# untitled.net
KiCad netlist of a schematic drawn in EAGLE
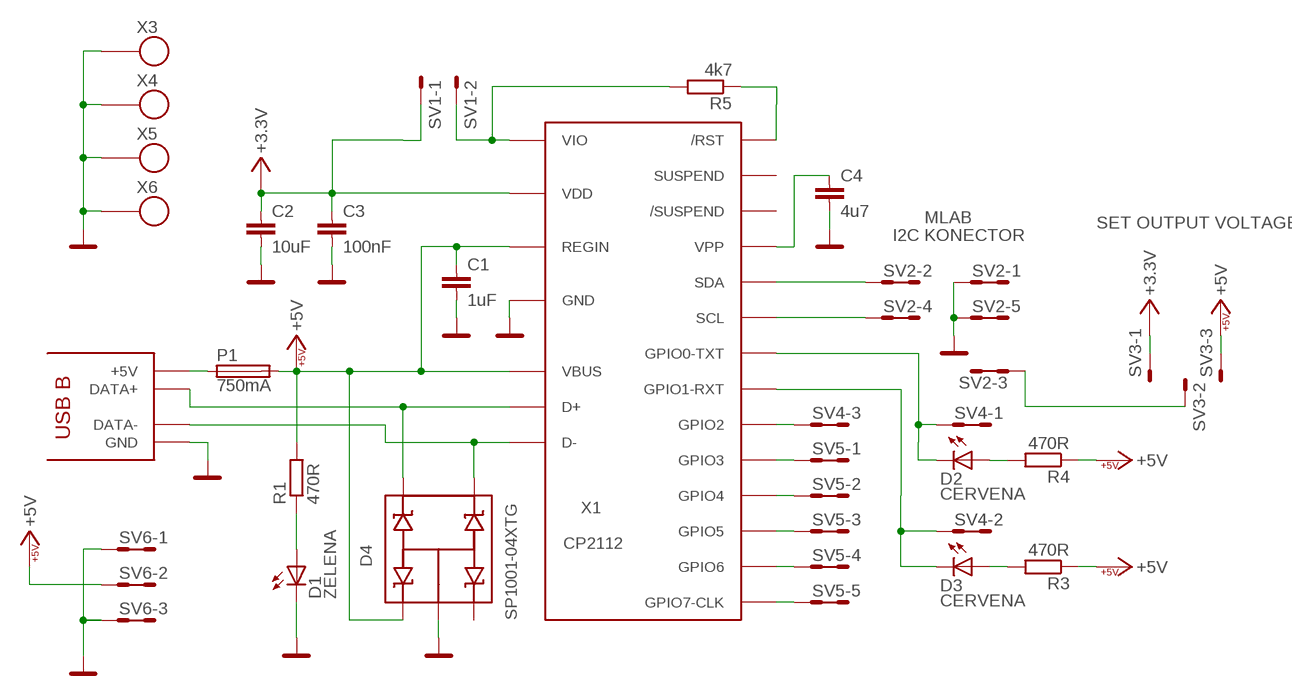
[diagram p0: schematic, sheet 1]

(export (version "E")
  (design (tool "Eeschema 10.0.6"))
  (components
    (comp (ref "C1")
      (value "1uF")
      (footprint "eagle-import:C0805")
      (libsource (lib "eagle-import") (part "C0805"))
    )
    (comp (ref "C2")
      (value "10uF")
      (footprint "eagle-import:C0805")
      (libsource (lib "eagle-import") (part "C0805"))
    )
    (comp (ref "C3")
      (value "100nF")
      (footprint "eagle-import:C0805")
      (libsource (lib "eagle-import") (part "C0805"))
    )
    (comp (ref "C4")
      (value "4u7")
      (footprint "eagle-import:C0805")
      (libsource (lib "eagle-import") (part "C0805"))
    )
    (comp (ref "D1")
      (value "ZELENA")
      (footprint "eagle-import:1206_2")
      (libsource (lib "eagle-import") (part "LED1206_2"))
    )
    (comp (ref "D2")
      (value "CERVENA")
      (footprint "eagle-import:1206_2")
      (libsource (lib "eagle-import") (part "LED1206_2"))
    )
    (comp (ref "D3")
      (value "CERVENA")
      (footprint "eagle-import:1206_2")
      (libsource (lib "eagle-import") (part "LED1206_2"))
    )
    (comp (ref "D4")
      (value "SP1001-04XTG")
      (footprint "eagle-import:SOT553")
      (libsource (lib "eagle-import") (part "CP2112"))
    )
    (comp (ref "P1")
      (value "750mA")
      (footprint "eagle-import:1812")
      (libsource (lib "eagle-import") (part "POJISTKA_1812"))
    )
    (comp (ref "R1")
      (value "470R")
      (footprint "eagle-import:0805")
      (libsource (lib "eagle-import") (part "R0805"))
    )
    (comp (ref "R3")
      (value "470R")
      (footprint "eagle-import:0805")
      (libsource (lib "eagle-import") (part "R0805"))
    )
    (comp (ref "R4")
      (value "470R")
      (footprint "eagle-import:0805")
      (libsource (lib "eagle-import") (part "R0805"))
    )
    (comp (ref "R5")
      (value "4k7")
      (footprint "eagle-import:0805")
      (libsource (lib "eagle-import") (part "R0805"))
    )
    (comp (ref "SV1")
      (value "MA02-1")
      (footprint "eagle-import:MA02-1")
      (libsource (lib "eagle-import") (part "MA02-1"))
    )
    (comp (ref "SV2")
      (value "MA05-2")
      (footprint "eagle-import:MA05-2")
      (libsource (lib "eagle-import") (part "MA05-2"))
    )
    (comp (ref "SV3")
      (value "MA03-1")
      (footprint "eagle-import:MA03-1")
      (libsource (lib "eagle-import") (part "MA03-1"))
    )
    (comp (ref "SV4")
      (value "MA03-2")
      (footprint "eagle-import:MA03-2")
      (libsource (lib "eagle-import") (part "MA03-2"))
    )
    (comp (ref "SV5")
      (value "MA05-2")
      (footprint "eagle-import:MA05-2")
      (libsource (lib "eagle-import") (part "MA05-2"))
    )
    (comp (ref "SV6")
      (value "MA03-2")
      (footprint "eagle-import:MA03-2")
      (libsource (lib "eagle-import") (part "MA03-2"))
    )
    (comp (ref "X1")
      (value "CP2112")
      (footprint "eagle-import:QFN-24")
      (libsource (lib "eagle-import") (part "moje_io_CP2112"))
    )
    (comp (ref "X2")
      (value "USB_B")
      (footprint "eagle-import:USB_B")
      (libsource (lib "eagle-import") (part "USB_B"))
    )
    (comp (ref "X3")
      (value "SROUB3M")
      (footprint "eagle-import:SROUB3M")
      (libsource (lib "eagle-import") (part "SROUB3M"))
    )
    (comp (ref "X4")
      (value "SROUB3M")
      (footprint "eagle-import:SROUB3M")
      (libsource (lib "eagle-import") (part "SROUB3M"))
    )
    (comp (ref "X5")
      (value "SROUB3M")
      (footprint "eagle-import:SROUB3M")
      (libsource (lib "eagle-import") (part "SROUB3M"))
    )
    (comp (ref "X6")
      (value "SROUB3M")
      (footprint "eagle-import:SROUB3M")
      (libsource (lib "eagle-import") (part "SROUB3M"))
    )
  )
  (nets
    (net (code "1") (name "+3.3V") (class "Default")
      (node (ref "C2") (pin "1") (pinfunction "1_1") (pintype "passive"))
      (node (ref "C3") (pin "1") (pinfunction "1_1") (pintype "passive"))
      (node (ref "SV1") (pin "1") (pinfunction "P$1_1") (pintype "passive"))
      (node (ref "SV3") (pin "1") (pinfunction "P$1_1") (pintype "passive"))
      (node (ref "X1") (pin "P$6") (pinfunction "VDD_P$6") (pintype "bidirectional"))
    )
    (net (code "2") (name "+5V") (class "Default")
      (node (ref "C1") (pin "1") (pinfunction "1_1") (pintype "passive"))
      (node (ref "D4") (pin "1") (pinfunction "P$1_1") (pintype "passive"))
      (node (ref "P1") (pin "2") (pinfunction "2_2") (pintype "passive"))
      (node (ref "R1") (pin "2") (pinfunction "2_2") (pintype "passive"))
      (node (ref "R3") (pin "1") (pinfunction "1_1") (pintype "passive"))
      (node (ref "R4") (pin "1") (pinfunction "1_1") (pintype "passive"))
      (node (ref "SV3") (pin "3") (pinfunction "P$1_3") (pintype "passive"))
      (node (ref "SV6") (pin "3") (pinfunction "K_3") (pintype "passive"))
      (node (ref "SV6") (pin "4") (pinfunction "K_4") (pintype "passive"))
      (node (ref "X1") (pin "P$7") (pinfunction "REGIN_P$7") (pintype "bidirectional"))
      (node (ref "X1") (pin "P$8") (pinfunction "VBUS_P$8") (pintype "bidirectional"))
    )
    (net (code "3") (name "GND") (class "Default")
      (node (ref "C1") (pin "2") (pinfunction "2_2") (pintype "passive"))
      (node (ref "C2") (pin "2") (pinfunction "2_2") (pintype "passive"))
      (node (ref "C3") (pin "2") (pinfunction "2_2") (pintype "passive"))
      (node (ref "C4") (pin "2") (pinfunction "2_2") (pintype "passive"))
      (node (ref "D1") (pin "K") (pinfunction "C_K") (pintype "passive"))
      (node (ref "D4") (pin "2") (pinfunction "P$2_2") (pintype "passive"))
      (node (ref "SV2") (pin "1") (pinfunction "K_1") (pintype "passive"))
      (node (ref "SV2") (pin "10") (pinfunction "K_10") (pintype "passive"))
      (node (ref "SV2") (pin "2") (pinfunction "K_2") (pintype "passive"))
      (node (ref "SV2") (pin "9") (pinfunction "K_9") (pintype "passive"))
      (node (ref "SV6") (pin "1") (pinfunction "K_1") (pintype "passive"))
      (node (ref "SV6") (pin "2") (pinfunction "K_2") (pintype "passive"))
      (node (ref "SV6") (pin "5") (pinfunction "K_5") (pintype "passive"))
      (node (ref "SV6") (pin "6") (pinfunction "K_6") (pintype "passive"))
      (node (ref "X1") (pin "P$2") (pinfunction "GND_P$2") (pintype "bidirectional"))
      (node (ref "X1") (pin "P$25") (pinfunction "GND_P$25") (pintype "bidirectional"))
      (node (ref "X2") (pin "4") (pinfunction "GND_4") (pintype "bidirectional"))
      (node (ref "X2") (pin "GND") (pinfunction "GND_GND") (pintype "bidirectional"))
      (node (ref "X2") (pin "GND2") (pinfunction "GND_GND2") (pintype "bidirectional"))
      (node (ref "X3") (pin "P$1") (pinfunction "P$1_P$1") (pintype "bidirectional"))
      (node (ref "X4") (pin "P$1") (pinfunction "P$1_P$1") (pintype "bidirectional"))
      (node (ref "X5") (pin "P$1") (pinfunction "P$1_P$1") (pintype "bidirectional"))
      (node (ref "X6") (pin "P$1") (pinfunction "P$1_P$1") (pintype "bidirectional"))
    )
    (net (code "4") (name "Net-(D1-PadA)") (class "Default")
      (node (ref "D1") (pin "A") (pinfunction "A_A") (pintype "passive"))
      (node (ref "R1") (pin "1") (pinfunction "1_1") (pintype "passive"))
    )
    (net (code "5") (name "Net-(D2-C)") (class "Default")
      (node (ref "D2") (pin "K") (pinfunction "C_K") (pintype "passive"))
      (node (ref "SV4") (pin "1") (pinfunction "K_1") (pintype "passive"))
      (node (ref "SV4") (pin "2") (pinfunction "K_2") (pintype "passive"))
      (node (ref "X1") (pin "P$23") (pinfunction "GPIO0-TXT_P$23") (pintype "bidirectional"))
    )
    (net (code "6") (name "Net-(D2-PadA)") (class "Default")
      (node (ref "D2") (pin "A") (pinfunction "A_A") (pintype "passive"))
      (node (ref "R4") (pin "2") (pinfunction "2_2") (pintype "passive"))
    )
    (net (code "7") (name "Net-(D3-C)") (class "Default")
      (node (ref "D3") (pin "K") (pinfunction "C_K") (pintype "passive"))
      (node (ref "SV4") (pin "3") (pinfunction "K_3") (pintype "passive"))
      (node (ref "SV4") (pin "4") (pinfunction "K_4") (pintype "passive"))
      (node (ref "X1") (pin "P$22") (pinfunction "GPIO1-RXT_P$22") (pintype "bidirectional"))
    )
    (net (code "8") (name "Net-(D3-PadA)") (class "Default")
      (node (ref "D3") (pin "A") (pinfunction "A_A") (pintype "passive"))
      (node (ref "R3") (pin "2") (pinfunction "2_2") (pintype "passive"))
    )
    (net (code "9") (name "Net-(D4-P$4)") (class "Default")
      (node (ref "D4") (pin "4") (pinfunction "P$4_4") (pintype "passive"))
      (node (ref "X1") (pin "P$4") (pinfunction "D-_P$4") (pintype "bidirectional"))
      (node (ref "X2") (pin "2") (pinfunction "DATA-_2") (pintype "bidirectional"))
    )
    (net (code "10") (name "Net-(D4-P$5)") (class "Default")
      (node (ref "D4") (pin "5") (pinfunction "P$5_5") (pintype "passive"))
      (node (ref "X1") (pin "P$3") (pinfunction "D+_P$3") (pintype "bidirectional"))
      (node (ref "X2") (pin "3") (pinfunction "DATA+_3") (pintype "bidirectional"))
    )
    (net (code "11") (name "Net-(SV1B-P$1)") (class "Default")
      (node (ref "R5") (pin "2") (pinfunction "2_2") (pintype "passive"))
      (node (ref "SV1") (pin "2") (pinfunction "P$1_2") (pintype "passive"))
      (node (ref "X1") (pin "P$5") (pinfunction "VIO_P$5") (pintype "bidirectional"))
    )
    (net (code "12") (name "Net-(SV3B-P$1)") (class "Default")
      (node (ref "SV2") (pin "5") (pinfunction "K_5") (pintype "passive"))
      (node (ref "SV2") (pin "6") (pinfunction "K_6") (pintype "passive"))
      (node (ref "SV3") (pin "2") (pinfunction "P$1_2") (pintype "passive"))
    )
    (net (code "13") (name "Net-(X1-GPIO2)") (class "Default")
      (node (ref "SV4") (pin "5") (pinfunction "K_5") (pintype "passive"))
      (node (ref "SV4") (pin "6") (pinfunction "K_6") (pintype "passive"))
      (node (ref "X1") (pin "P$21") (pinfunction "GPIO2_P$21") (pintype "bidirectional"))
    )
    (net (code "14") (name "Net-(X1-GPIO3)") (class "Default")
      (node (ref "SV5") (pin "1") (pinfunction "K_1") (pintype "passive"))
      (node (ref "SV5") (pin "2") (pinfunction "K_2") (pintype "passive"))
      (node (ref "X1") (pin "P$20") (pinfunction "GPIO3_P$20") (pintype "bidirectional"))
    )
    (net (code "15") (name "Net-(X1-GPIO4)") (class "Default")
      (node (ref "SV5") (pin "3") (pinfunction "K_3") (pintype "passive"))
      (node (ref "SV5") (pin "4") (pinfunction "K_4") (pintype "passive"))
      (node (ref "X1") (pin "P$15") (pinfunction "GPIO4_P$15") (pintype "bidirectional"))
    )
    (net (code "16") (name "Net-(X1-GPIO5)") (class "Default")
      (node (ref "SV5") (pin "5") (pinfunction "K_5") (pintype "passive"))
      (node (ref "SV5") (pin "6") (pinfunction "K_6") (pintype "passive"))
      (node (ref "X1") (pin "P$14") (pinfunction "GPIO5_P$14") (pintype "bidirectional"))
    )
    (net (code "17") (name "Net-(X1-GPIO6)") (class "Default")
      (node (ref "SV5") (pin "7") (pinfunction "K_7") (pintype "passive"))
      (node (ref "SV5") (pin "8") (pinfunction "K_8") (pintype "passive"))
      (node (ref "X1") (pin "P$13") (pinfunction "GPIO6_P$13") (pintype "bidirectional"))
    )
    (net (code "18") (name "Net-(X1-GPIO7-CLK)") (class "Default")
      (node (ref "SV5") (pin "10") (pinfunction "K_10") (pintype "passive"))
      (node (ref "SV5") (pin "9") (pinfunction "K_9") (pintype "passive"))
      (node (ref "X1") (pin "P$12") (pinfunction "GPIO7-CLK_P$12") (pintype "bidirectional"))
    )
    (net (code "19") (name "Net-(X1-SCL)") (class "Default")
      (node (ref "SV2") (pin "7") (pinfunction "K_7") (pintype "passive"))
      (node (ref "SV2") (pin "8") (pinfunction "K_8") (pintype "passive"))
      (node (ref "X1") (pin "P$24") (pinfunction "SCL_P$24") (pintype "bidirectional"))
    )
    (net (code "20") (name "Net-(X1-SDA)") (class "Default")
      (node (ref "SV2") (pin "3") (pinfunction "K_3") (pintype "passive"))
      (node (ref "SV2") (pin "4") (pinfunction "K_4") (pintype "passive"))
      (node (ref "X1") (pin "P$1") (pinfunction "SDA_P$1") (pintype "bidirectional"))
    )
    (net (code "21") (name "Net-(X1-VPP)") (class "Default")
      (node (ref "C4") (pin "1") (pinfunction "1_1") (pintype "passive"))
      (node (ref "X1") (pin "P$16") (pinfunction "VPP_P$16") (pintype "bidirectional"))
    )
    (net (code "22") (name "Net-(X1-{slash}RST)") (class "Default")
      (node (ref "R5") (pin "1") (pinfunction "1_1") (pintype "passive"))
      (node (ref "X1") (pin "P$9") (pinfunction "/RST_P$9") (pintype "bidirectional"))
    )
    (net (code "23") (name "Net-(X2-+5V)") (class "Default")
      (node (ref "P1") (pin "1") (pinfunction "1_1") (pintype "passive"))
      (node (ref "X2") (pin "1") (pinfunction "+5V_1") (pintype "bidirectional"))
    )
    (net (code "24") (name "unconnected-(D4-P$3-Pad3)") (class "Default")
      (node (ref "D4") (pin "3") (pinfunction "P$3_3") (pintype "passive"))
    )
    (net (code "25") (name "unconnected-(X1-SUSPEND-PadP$11)") (class "Default")
      (node (ref "X1") (pin "P$11") (pinfunction "SUSPEND_P$11") (pintype "bidirectional"))
    )
    (net (code "26") (name "unconnected-(X1-{slash}SUSPEND-PadP$17)") (class "Default")
      (node (ref "X1") (pin "P$17") (pinfunction "/SUSPEND_P$17") (pintype "bidirectional"))
    )
  )
)
